# AST1033.net
KiCad netlist of a schematic drawn in EAGLE
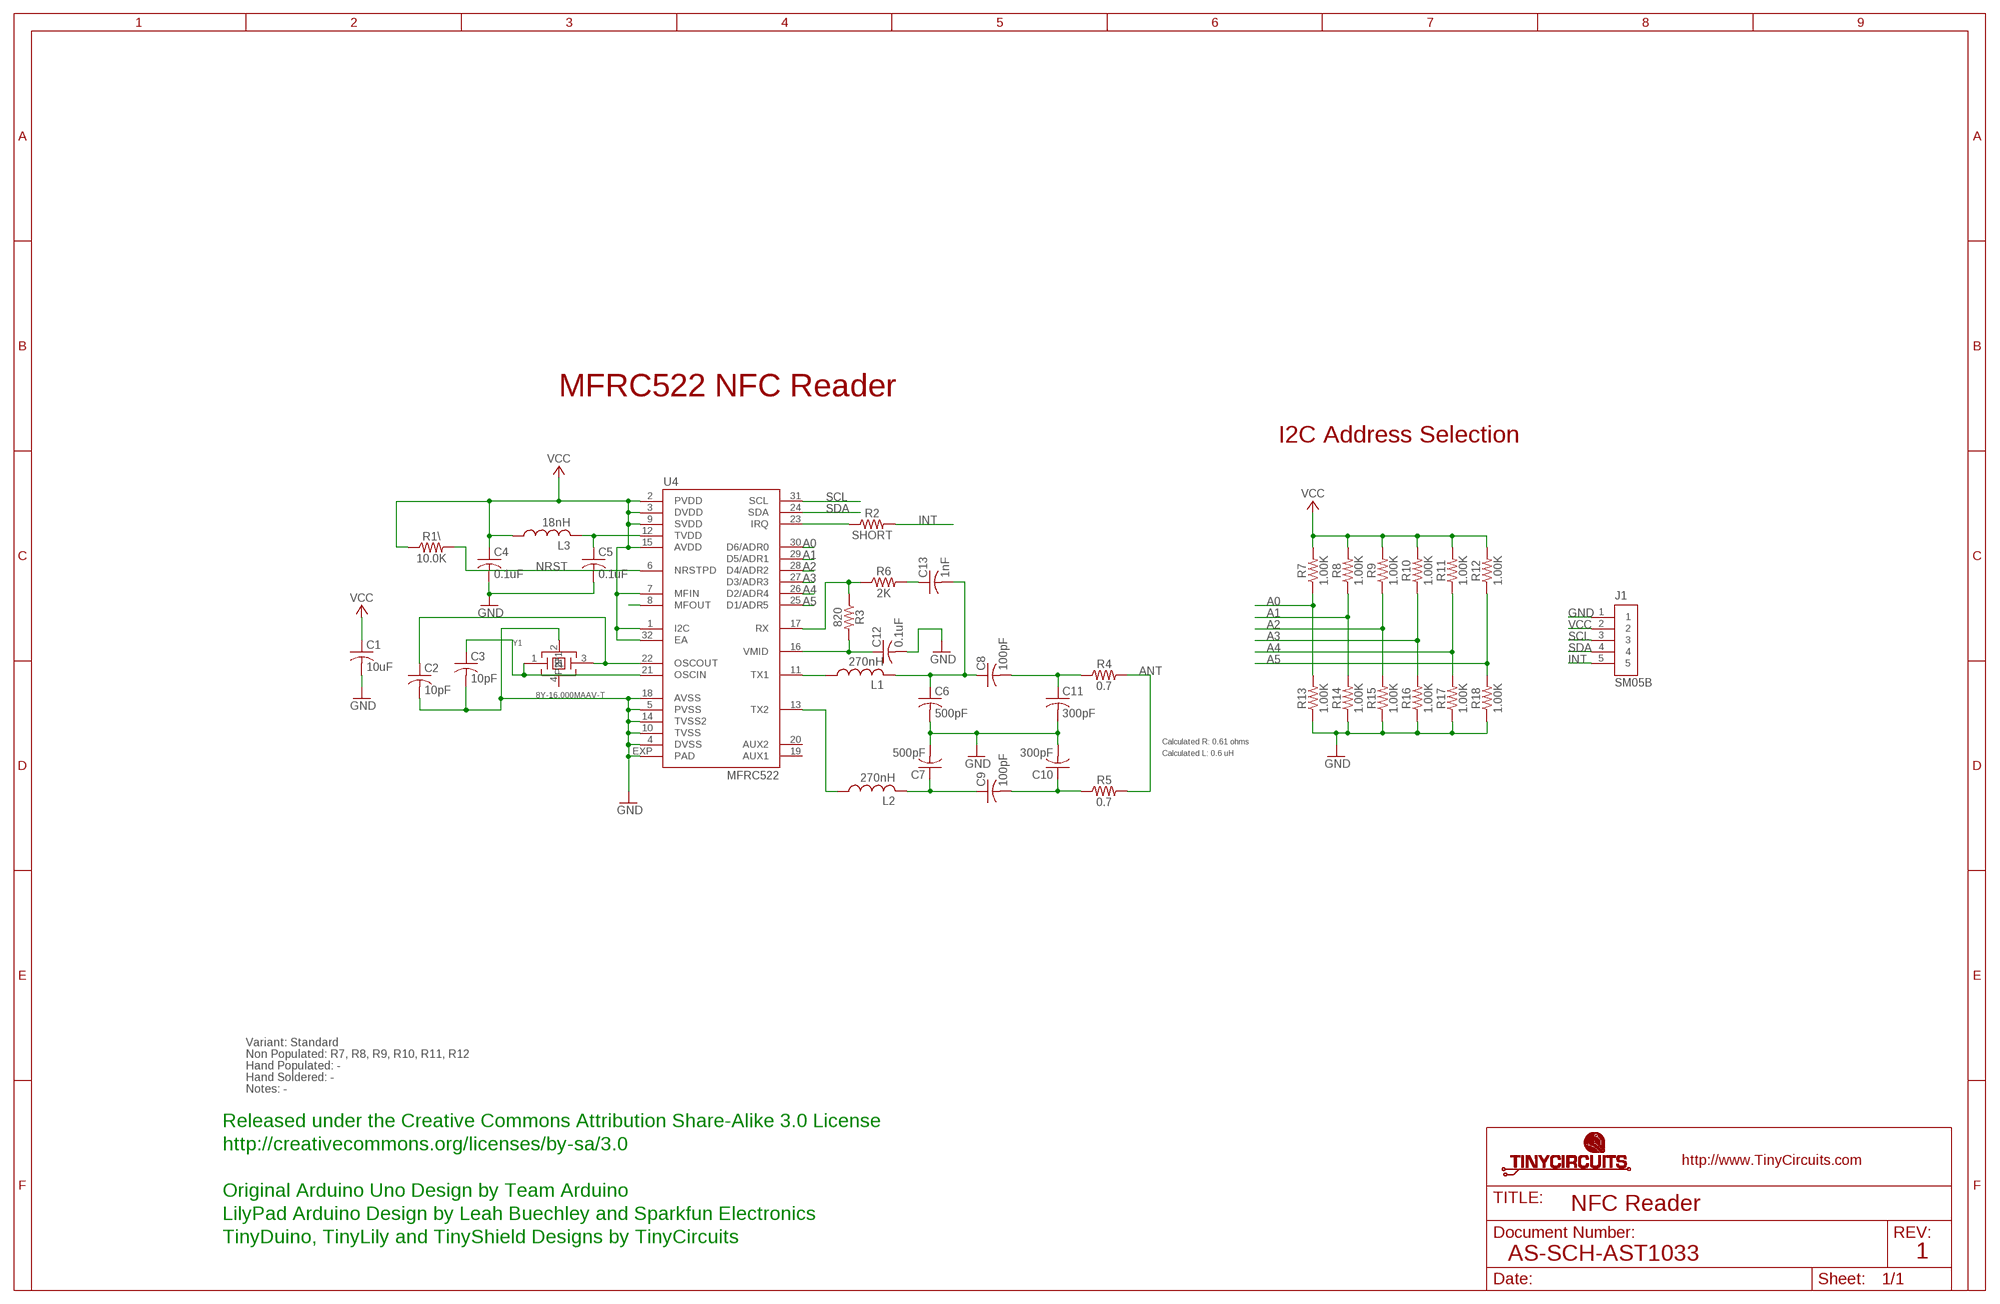
[diagram p0: schematic, sheet 1]

(export (version "E")
  (design (tool "Eeschema 10.0.6"))
  (components
    (comp (ref "C1")
      (value "10uF")
      (footprint "eagle-import:C0603")
      (fields (field (name "PARTNO") "AS-ITM-00002") (field (name "PARTNO_1") "AS-ITM-00002"))
      (libsource (lib "eagle-import") (part "AS-ITM-00002"))
    )
    (comp (ref "C2")
      (value "10pF")
      (footprint "eagle-import:C0402")
      (fields (field (name "PARTNO") "AS-ITM-00261"))
      (libsource (lib "eagle-import") (part "AS-ITM-00261"))
    )
    (comp (ref "C3")
      (value "10pF")
      (footprint "eagle-import:C0402")
      (fields (field (name "PARTNO") "AS-ITM-00261"))
      (libsource (lib "eagle-import") (part "AS-ITM-00261"))
    )
    (comp (ref "C4")
      (value "0.1uF")
      (footprint "eagle-import:C0402")
      (fields (field (name "PARTNO") "AS-ITM-00008") (field (name "PARTNO_1") "AS-ITM-00008"))
      (libsource (lib "eagle-import") (part "AS-ITM-00008"))
    )
    (comp (ref "C5")
      (value "0.1uF")
      (footprint "eagle-import:C0402")
      (fields (field (name "PARTNO") "AS-ITM-00008") (field (name "PARTNO_1") "AS-ITM-00008"))
      (libsource (lib "eagle-import") (part "AS-ITM-00008"))
    )
    (comp (ref "C6")
      (value "500pF")
      (footprint "eagle-import:0402")
      (fields (field (name "PARTNO") "AS-ITM-00148") (field (name "PARTNO_1") "AS-ITM-00148"))
      (libsource (lib "eagle-import") (part "AS-ITM-00148"))
    )
    (comp (ref "C7")
      (value "500pF")
      (footprint "eagle-import:0402")
      (fields (field (name "PARTNO") "AS-ITM-00148") (field (name "PARTNO_1") "AS-ITM-00148"))
      (libsource (lib "eagle-import") (part "AS-ITM-00148"))
    )
    (comp (ref "C8")
      (value "100pF")
      (footprint "eagle-import:0402")
      (fields (field (name "PARTNO") "AS-ITM-00148") (field (name "PARTNO_1") "AS-ITM-00148"))
      (libsource (lib "eagle-import") (part "AS-ITM-00148"))
    )
    (comp (ref "C9")
      (value "100pF")
      (footprint "eagle-import:0402")
      (fields (field (name "PARTNO") "AS-ITM-00148") (field (name "PARTNO_1") "AS-ITM-00148"))
      (libsource (lib "eagle-import") (part "AS-ITM-00148"))
    )
    (comp (ref "C10")
      (value "300pF")
      (footprint "eagle-import:C0402")
      (fields (field (name "PARTNO") "AS-ITM-00008") (field (name "PARTNO_1") "AS-ITM-00008"))
      (libsource (lib "eagle-import") (part "AS-ITM-00008"))
    )
    (comp (ref "C11")
      (value "300pF")
      (footprint "eagle-import:C0402")
      (fields (field (name "PARTNO") "AS-ITM-00008") (field (name "PARTNO_1") "AS-ITM-00008"))
      (libsource (lib "eagle-import") (part "AS-ITM-00008"))
    )
    (comp (ref "C12")
      (value "0.1uF")
      (footprint "eagle-import:C0402")
      (fields (field (name "PARTNO") "AS-ITM-00008") (field (name "PARTNO_1") "AS-ITM-00008"))
      (libsource (lib "eagle-import") (part "AS-ITM-00008"))
    )
    (comp (ref "C13")
      (value "1nF")
      (footprint "eagle-import:C0402")
      (fields (field (name "PARTNO") "AS-ITM-00008") (field (name "PARTNO_1") "AS-ITM-00008"))
      (libsource (lib "eagle-import") (part "AS-ITM-00008"))
    )
    (comp (ref "J1")
      (value "SM05B")
      (footprint "eagle-import:JST_SH_5X1")
      (fields (field (name "PARTNO") "AS-ITM-00340"))
      (libsource (lib "eagle-import") (part "AS-ITM-00340"))
    )
    (comp (ref "L1")
      (value "270nH")
      (footprint "eagle-import:C0402")
      (fields (field (name "PARTNO") "AS-ITM-00250") (field (name "PARTNO_1") "AS-ITM-00250"))
      (libsource (lib "eagle-import") (part "AS-ITM-00250"))
    )
    (comp (ref "L2")
      (value "270nH")
      (footprint "eagle-import:C0402")
      (fields (field (name "PARTNO") "AS-ITM-00250") (field (name "PARTNO_1") "AS-ITM-00250"))
      (libsource (lib "eagle-import") (part "AS-ITM-00250"))
    )
    (comp (ref "L3")
      (value "18nH")
      (footprint "eagle-import:C0402")
      (fields (field (name "PARTNO") "AS-ITM-00260"))
      (libsource (lib "eagle-import") (part "AS-ITM-00260"))
    )
    (comp (ref "R1\\")
      (value "10.0K")
      (footprint "eagle-import:0402")
      (fields (field (name "PARTNO") "AS-ITM-00032"))
      (libsource (lib "eagle-import") (part "AS-ITM-00032"))
    )
    (comp (ref "R2")
      (value "SHORT")
      (footprint "eagle-import:0402_SHORT")
      (fields (field (name "PARTNO") "AS-ITM-00076"))
      (libsource (lib "eagle-import") (part "AS-ITM-000760402_SHORT"))
    )
    (comp (ref "R3")
      (value "820")
      (footprint "eagle-import:0402")
      (fields (field (name "PARTNO") "AS-ITM-00076") (field (name "PARTNO_1") "AS-ITM-00076"))
      (libsource (lib "eagle-import") (part "AS-ITM-00076"))
    )
    (comp (ref "R4")
      (value "0.7")
      (footprint "eagle-import:0402")
      (fields (field (name "PARTNO") "AS-ITM-00076"))
      (libsource (lib "eagle-import") (part "AS-ITM-00076"))
    )
    (comp (ref "R5")
      (value "0.7")
      (footprint "eagle-import:0402")
      (fields (field (name "PARTNO") "AS-ITM-00076"))
      (libsource (lib "eagle-import") (part "AS-ITM-00076"))
    )
    (comp (ref "R6")
      (value "2K")
      (footprint "eagle-import:0402")
      (fields (field (name "PARTNO") "AS-ITM-00315") (field (name "PARTNO_1") "AS-ITM-00315"))
      (libsource (lib "eagle-import") (part "AS-ITM-00315"))
    )
    (comp (ref "R7")
      (value "1.00K")
      (footprint "eagle-import:0402")
      (fields (field (name "PARTNO") "AS-ITM-00003"))
      (libsource (lib "eagle-import") (part "AS-ITM-00003"))
    )
    (comp (ref "R8")
      (value "1.00K")
      (footprint "eagle-import:0402")
      (fields (field (name "PARTNO") "AS-ITM-00003"))
      (libsource (lib "eagle-import") (part "AS-ITM-00003"))
    )
    (comp (ref "R9")
      (value "1.00K")
      (footprint "eagle-import:0402")
      (fields (field (name "PARTNO") "AS-ITM-00003"))
      (libsource (lib "eagle-import") (part "AS-ITM-00003"))
    )
    (comp (ref "R10")
      (value "1.00K")
      (footprint "eagle-import:0402")
      (fields (field (name "PARTNO") "AS-ITM-00003"))
      (libsource (lib "eagle-import") (part "AS-ITM-00003"))
    )
    (comp (ref "R11")
      (value "1.00K")
      (footprint "eagle-import:0402")
      (fields (field (name "PARTNO") "AS-ITM-00003"))
      (libsource (lib "eagle-import") (part "AS-ITM-00003"))
    )
    (comp (ref "R12")
      (value "1.00K")
      (footprint "eagle-import:0402")
      (fields (field (name "PARTNO") "AS-ITM-00003"))
      (libsource (lib "eagle-import") (part "AS-ITM-00003"))
    )
    (comp (ref "R13")
      (value "1.00K")
      (footprint "eagle-import:0402")
      (fields (field (name "PARTNO") "AS-ITM-00003"))
      (libsource (lib "eagle-import") (part "AS-ITM-00003"))
    )
    (comp (ref "R14")
      (value "1.00K")
      (footprint "eagle-import:0402")
      (fields (field (name "PARTNO") "AS-ITM-00003"))
      (libsource (lib "eagle-import") (part "AS-ITM-00003"))
    )
    (comp (ref "R15")
      (value "1.00K")
      (footprint "eagle-import:0402")
      (fields (field (name "PARTNO") "AS-ITM-00003"))
      (libsource (lib "eagle-import") (part "AS-ITM-00003"))
    )
    (comp (ref "R16")
      (value "1.00K")
      (footprint "eagle-import:0402")
      (fields (field (name "PARTNO") "AS-ITM-00003"))
      (libsource (lib "eagle-import") (part "AS-ITM-00003"))
    )
    (comp (ref "R17")
      (value "1.00K")
      (footprint "eagle-import:0402")
      (fields (field (name "PARTNO") "AS-ITM-00003"))
      (libsource (lib "eagle-import") (part "AS-ITM-00003"))
    )
    (comp (ref "R18")
      (value "1.00K")
      (footprint "eagle-import:0402")
      (fields (field (name "PARTNO") "AS-ITM-00003"))
      (libsource (lib "eagle-import") (part "AS-ITM-00003"))
    )
    (comp (ref "U4")
      (value "MFRC522")
      (footprint "eagle-import:ATMEL_QFN32")
      (fields (field (name "PARTNO") "AS-ITM-00293"))
      (libsource (lib "eagle-import") (part "AS-ITM-00293"))
    )
    (comp (ref "Y1")
      (value "8Y-16.000MAAV-T")
      (footprint "eagle-import:ABM11")
      (fields (field (name "PARTNO") "AS-ITM-00228"))
      (libsource (lib "eagle-import") (part "AS-ITM-00228"))
    )
  )
  (nets
    (net (code "1") (name "/A0") (class "Default")
      (node (ref "R13") (pin "2") (pinfunction "2_2") (pintype "passive"))
      (node (ref "R7") (pin "1") (pinfunction "1_1") (pintype "passive"))
      (node (ref "U4") (pin "30") (pinfunction "D6/ADR0_30") (pintype "bidirectional"))
    )
    (net (code "2") (name "/A1") (class "Default")
      (node (ref "R14") (pin "2") (pinfunction "2_2") (pintype "passive"))
      (node (ref "R8") (pin "1") (pinfunction "1_1") (pintype "passive"))
      (node (ref "U4") (pin "29") (pinfunction "D5/ADR1_29") (pintype "bidirectional"))
    )
    (net (code "3") (name "/A2") (class "Default")
      (node (ref "R15") (pin "2") (pinfunction "2_2") (pintype "passive"))
      (node (ref "R9") (pin "1") (pinfunction "1_1") (pintype "passive"))
      (node (ref "U4") (pin "28") (pinfunction "D4/ADR2_28") (pintype "bidirectional"))
    )
    (net (code "4") (name "/A3") (class "Default")
      (node (ref "R10") (pin "1") (pinfunction "1_1") (pintype "passive"))
      (node (ref "R16") (pin "2") (pinfunction "2_2") (pintype "passive"))
      (node (ref "U4") (pin "27") (pinfunction "D3/ADR3_27") (pintype "bidirectional"))
    )
    (net (code "5") (name "/A4") (class "Default")
      (node (ref "R11") (pin "1") (pinfunction "1_1") (pintype "passive"))
      (node (ref "R17") (pin "2") (pinfunction "2_2") (pintype "passive"))
      (node (ref "U4") (pin "26") (pinfunction "D2/ADR4_26") (pintype "bidirectional"))
    )
    (net (code "6") (name "/A5") (class "Default")
      (node (ref "R12") (pin "1") (pinfunction "1_1") (pintype "passive"))
      (node (ref "R18") (pin "2") (pinfunction "2_2") (pintype "passive"))
      (node (ref "U4") (pin "25") (pinfunction "D1/ADR5_25") (pintype "bidirectional"))
    )
    (net (code "7") (name "/ANT") (class "Default")
      (node (ref "R4") (pin "2") (pinfunction "2_2") (pintype "passive"))
      (node (ref "R5") (pin "2") (pinfunction "2_2") (pintype "passive"))
    )
    (net (code "8") (name "/INT") (class "Default")
      (node (ref "J1") (pin "5") (pinfunction "5_5") (pintype "bidirectional"))
      (node (ref "R2") (pin "2") (pinfunction "2_2") (pintype "passive"))
    )
    (net (code "9") (name "/NRST") (class "Default")
      (node (ref "R1\\") (pin "2") (pinfunction "2_2") (pintype "passive"))
      (node (ref "U4") (pin "6") (pinfunction "NRSTPD_6") (pintype "bidirectional"))
    )
    (net (code "10") (name "/SCL") (class "Default")
      (node (ref "J1") (pin "3") (pinfunction "3_3") (pintype "bidirectional"))
      (node (ref "U4") (pin "31") (pinfunction "SCL_31") (pintype "bidirectional"))
    )
    (net (code "11") (name "/SDA") (class "Default")
      (node (ref "J1") (pin "4") (pinfunction "4_4") (pintype "bidirectional"))
      (node (ref "U4") (pin "24") (pinfunction "SDA_24") (pintype "bidirectional"))
    )
    (net (code "12") (name "GND") (class "Default")
      (node (ref "C1") (pin "2") (pinfunction "2_2") (pintype "passive"))
      (node (ref "C10") (pin "2") (pinfunction "2_2") (pintype "passive"))
      (node (ref "C11") (pin "2") (pinfunction "2_2") (pintype "passive"))
      (node (ref "C12") (pin "2") (pinfunction "2_2") (pintype "passive"))
      (node (ref "C2") (pin "2") (pinfunction "2_2") (pintype "passive"))
      (node (ref "C3") (pin "2") (pinfunction "2_2") (pintype "passive"))
      (node (ref "C4") (pin "2") (pinfunction "2_2") (pintype "passive"))
      (node (ref "C5") (pin "2") (pinfunction "2_2") (pintype "passive"))
      (node (ref "C6") (pin "2") (pinfunction "2_2") (pintype "passive"))
      (node (ref "C7") (pin "2") (pinfunction "2_2") (pintype "passive"))
      (node (ref "J1") (pin "1") (pinfunction "1_1") (pintype "bidirectional"))
      (node (ref "R13") (pin "1") (pinfunction "1_1") (pintype "passive"))
      (node (ref "R14") (pin "1") (pinfunction "1_1") (pintype "passive"))
      (node (ref "R15") (pin "1") (pinfunction "1_1") (pintype "passive"))
      (node (ref "R16") (pin "1") (pinfunction "1_1") (pintype "passive"))
      (node (ref "R17") (pin "1") (pinfunction "1_1") (pintype "passive"))
      (node (ref "R18") (pin "1") (pinfunction "1_1") (pintype "passive"))
      (node (ref "U4") (pin "10") (pinfunction "TVSS_10") (pintype "bidirectional"))
      (node (ref "U4") (pin "14") (pinfunction "TVSS2_14") (pintype "bidirectional"))
      (node (ref "U4") (pin "18") (pinfunction "AVSS_18") (pintype "bidirectional"))
      (node (ref "U4") (pin "4") (pinfunction "DVSS_4") (pintype "bidirectional"))
      (node (ref "U4") (pin "5") (pinfunction "PVSS_5") (pintype "bidirectional"))
      (node (ref "U4") (pin "EXP") (pinfunction "PAD_EXP") (pintype "bidirectional"))
      (node (ref "Y1") (pin "2") (pinfunction "P2_2") (pintype "bidirectional"))
    )
    (net (code "13") (name "Net-(C7-Pad1)") (class "Default")
      (node (ref "C7") (pin "1") (pinfunction "1_1") (pintype "passive"))
      (node (ref "C9") (pin "1") (pinfunction "1_1") (pintype "passive"))
      (node (ref "L2") (pin "2") (pinfunction "2_2") (pintype "passive"))
    )
    (net (code "14") (name "Net-(C10-Pad1)") (class "Default")
      (node (ref "C10") (pin "1") (pinfunction "1_1") (pintype "passive"))
      (node (ref "C9") (pin "2") (pinfunction "2_2") (pintype "passive"))
      (node (ref "R5") (pin "1") (pinfunction "1_1") (pintype "passive"))
    )
    (net (code "15") (name "Net-(C11-Pad1)") (class "Default")
      (node (ref "C11") (pin "1") (pinfunction "1_1") (pintype "passive"))
      (node (ref "C8") (pin "2") (pinfunction "2_2") (pintype "passive"))
      (node (ref "R4") (pin "1") (pinfunction "1_1") (pintype "passive"))
    )
    (net (code "16") (name "Net-(C13-Pad1)") (class "Default")
      (node (ref "C13") (pin "1") (pinfunction "1_1") (pintype "passive"))
      (node (ref "R6") (pin "2") (pinfunction "2_2") (pintype "passive"))
    )
    (net (code "17") (name "Net-(C13-Pad2)") (class "Default")
      (node (ref "C13") (pin "2") (pinfunction "2_2") (pintype "passive"))
      (node (ref "C6") (pin "1") (pinfunction "1_1") (pintype "passive"))
      (node (ref "C8") (pin "1") (pinfunction "1_1") (pintype "passive"))
      (node (ref "L1") (pin "2") (pinfunction "2_2") (pintype "passive"))
    )
    (net (code "18") (name "Net-(U4-IRQ)") (class "Default")
      (node (ref "R2") (pin "1") (pinfunction "1_1") (pintype "passive"))
      (node (ref "U4") (pin "23") (pinfunction "IRQ_23") (pintype "bidirectional"))
    )
    (net (code "19") (name "Net-(U4-OSCIN)") (class "Default")
      (node (ref "C3") (pin "1") (pinfunction "1_1") (pintype "passive"))
      (node (ref "U4") (pin "21") (pinfunction "OSCIN_21") (pintype "bidirectional"))
      (node (ref "Y1") (pin "1") (pinfunction "1_1") (pintype "bidirectional"))
    )
    (net (code "20") (name "Net-(U4-OSCOUT)") (class "Default")
      (node (ref "C2") (pin "1") (pinfunction "1_1") (pintype "passive"))
      (node (ref "U4") (pin "22") (pinfunction "OSCOUT_22") (pintype "bidirectional"))
      (node (ref "Y1") (pin "3") (pinfunction "2_3") (pintype "bidirectional"))
    )
    (net (code "21") (name "Net-(U4-RX)") (class "Default")
      (node (ref "R3") (pin "1") (pinfunction "1_1") (pintype "passive"))
      (node (ref "R6") (pin "1") (pinfunction "1_1") (pintype "passive"))
      (node (ref "U4") (pin "17") (pinfunction "RX_17") (pintype "bidirectional"))
    )
    (net (code "22") (name "Net-(U4-TVDD)") (class "Default")
      (node (ref "C5") (pin "1") (pinfunction "1_1") (pintype "passive"))
      (node (ref "L3") (pin "2") (pinfunction "2_2") (pintype "passive"))
      (node (ref "U4") (pin "12") (pinfunction "TVDD_12") (pintype "bidirectional"))
    )
    (net (code "23") (name "Net-(U4-TX1)") (class "Default")
      (node (ref "L1") (pin "1") (pinfunction "1_1") (pintype "passive"))
      (node (ref "U4") (pin "11") (pinfunction "TX1_11") (pintype "bidirectional"))
    )
    (net (code "24") (name "Net-(U4-TX2)") (class "Default")
      (node (ref "L2") (pin "1") (pinfunction "1_1") (pintype "passive"))
      (node (ref "U4") (pin "13") (pinfunction "TX2_13") (pintype "bidirectional"))
    )
    (net (code "25") (name "Net-(U4-VMID)") (class "Default")
      (node (ref "C12") (pin "1") (pinfunction "1_1") (pintype "passive"))
      (node (ref "R3") (pin "2") (pinfunction "2_2") (pintype "passive"))
      (node (ref "U4") (pin "16") (pinfunction "VMID_16") (pintype "bidirectional"))
    )
    (net (code "26") (name "VCC") (class "Default")
      (node (ref "C1") (pin "1") (pinfunction "1_1") (pintype "passive"))
      (node (ref "C4") (pin "1") (pinfunction "1_1") (pintype "passive"))
      (node (ref "J1") (pin "2") (pinfunction "2_2") (pintype "bidirectional"))
      (node (ref "L3") (pin "1") (pinfunction "1_1") (pintype "passive"))
      (node (ref "R10") (pin "2") (pinfunction "2_2") (pintype "passive"))
      (node (ref "R11") (pin "2") (pinfunction "2_2") (pintype "passive"))
      (node (ref "R12") (pin "2") (pinfunction "2_2") (pintype "passive"))
      (node (ref "R1\\") (pin "1") (pinfunction "1_1") (pintype "passive"))
      (node (ref "R7") (pin "2") (pinfunction "2_2") (pintype "passive"))
      (node (ref "R8") (pin "2") (pinfunction "2_2") (pintype "passive"))
      (node (ref "R9") (pin "2") (pinfunction "2_2") (pintype "passive"))
      (node (ref "U4") (pin "1") (pinfunction "I2C_1") (pintype "bidirectional"))
      (node (ref "U4") (pin "15") (pinfunction "AVDD_15") (pintype "bidirectional"))
      (node (ref "U4") (pin "2") (pinfunction "PVDD_2") (pintype "bidirectional"))
      (node (ref "U4") (pin "3") (pinfunction "DVDD_3") (pintype "bidirectional"))
      (node (ref "U4") (pin "32") (pinfunction "EA_32") (pintype "bidirectional"))
      (node (ref "U4") (pin "7") (pinfunction "MFIN_7") (pintype "bidirectional"))
      (node (ref "U4") (pin "9") (pinfunction "SVDD_9") (pintype "bidirectional"))
    )
    (net (code "27") (name "unconnected-(U4-AUX1-Pad19)") (class "Default")
      (node (ref "U4") (pin "19") (pinfunction "AUX1_19") (pintype "bidirectional"))
    )
    (net (code "28") (name "unconnected-(U4-AUX2-Pad20)") (class "Default")
      (node (ref "U4") (pin "20") (pinfunction "AUX2_20") (pintype "bidirectional"))
    )
    (net (code "29") (name "unconnected-(U4-MFOUT-Pad8)") (class "Default")
      (node (ref "U4") (pin "8") (pinfunction "MFOUT_8") (pintype "bidirectional"))
    )
    (net (code "30") (name "unconnected-(Y1-P1-Pad4)") (class "Default")
      (node (ref "Y1") (pin "4") (pinfunction "P1_4") (pintype "bidirectional"))
    )
  )
)
